# phatdapter.net
KiCad netlist of a schematic drawn in EAGLE
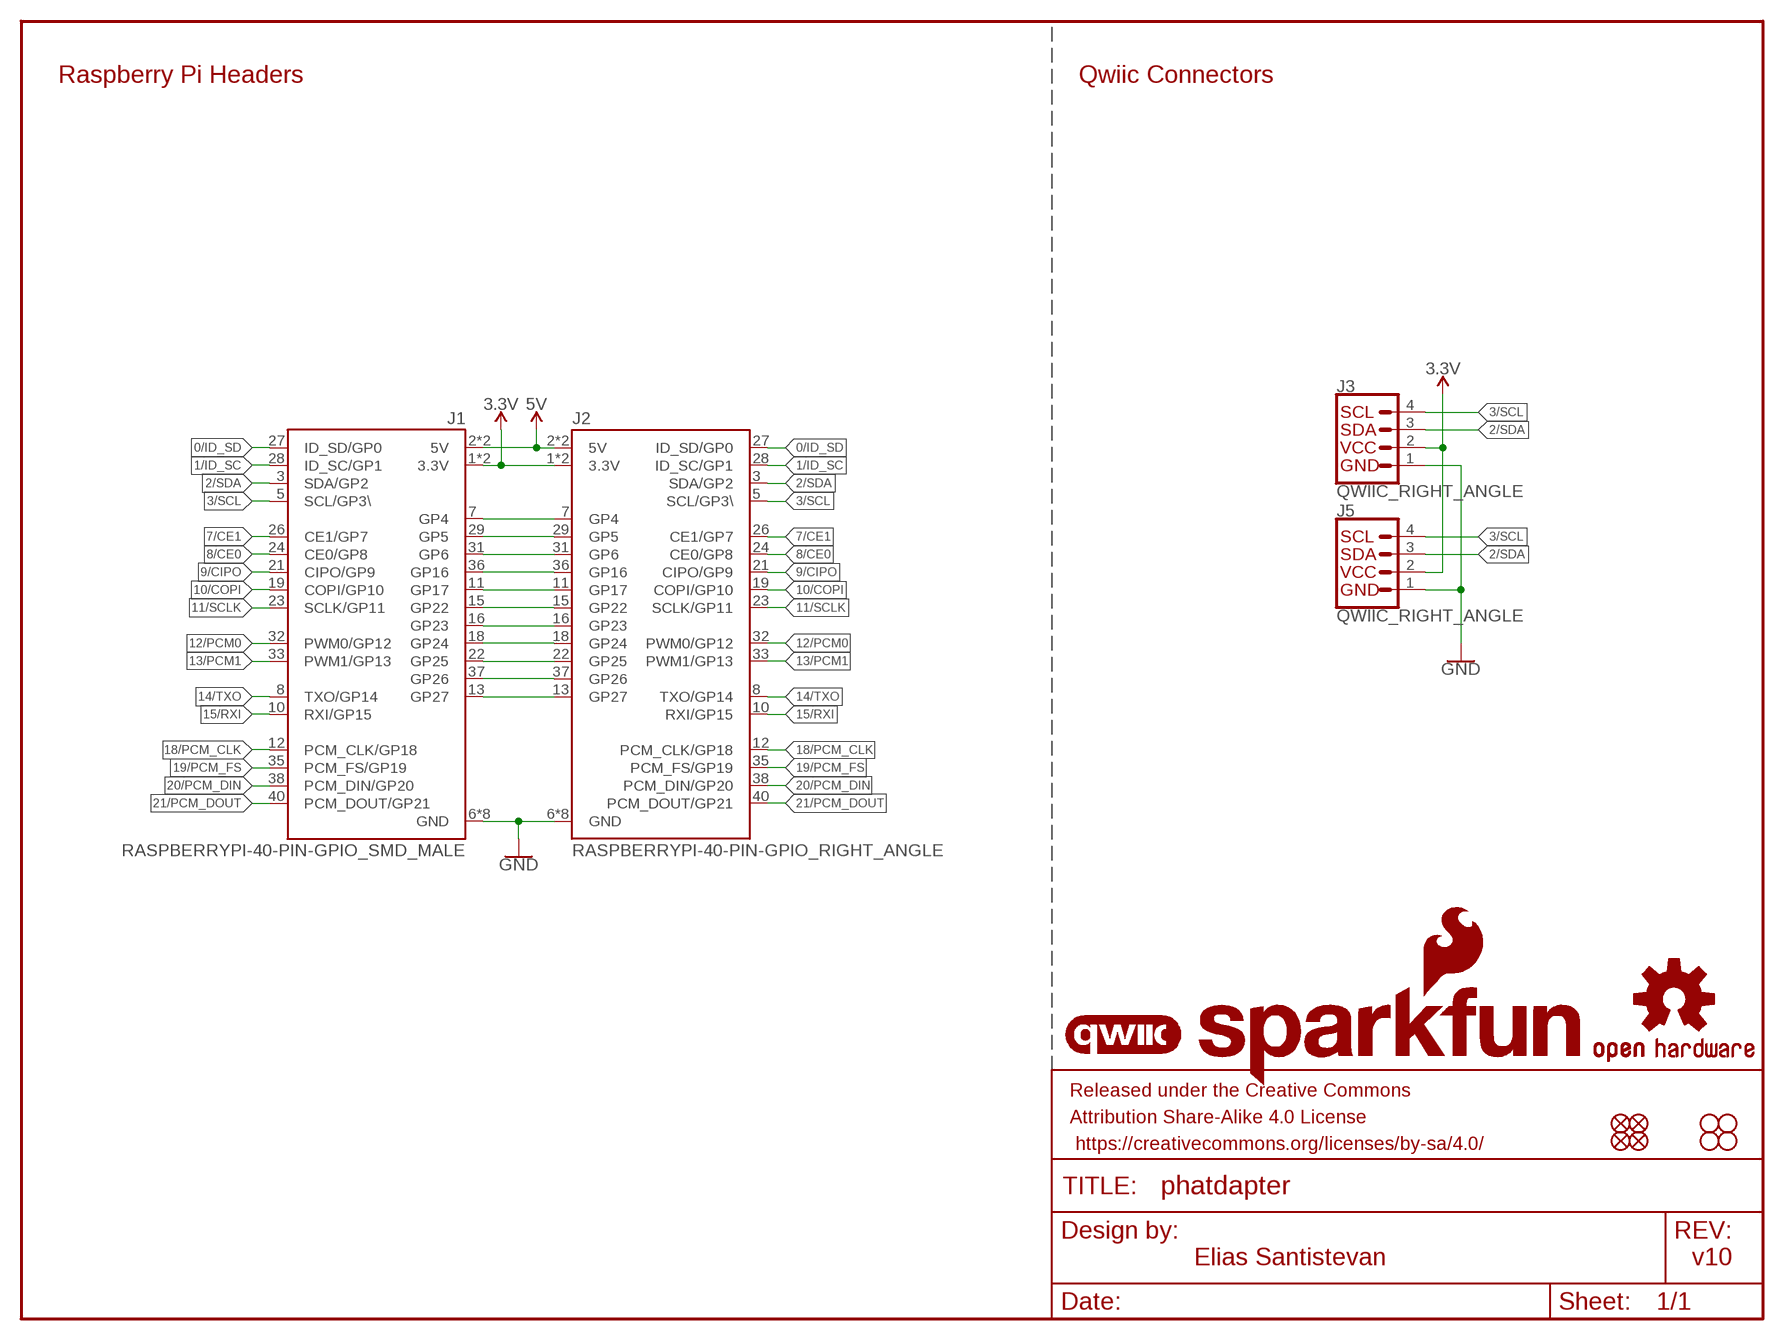
[diagram p0: schematic, sheet 1]

(export (version "E")
  (design (tool "Eeschema 10.0.6"))
  (components
    (comp (ref "FD1")
      (value "FIDUCIALUFIDUCIAL")
      (footprint "eagle-import:FIDUCIAL-MICRO")
      (libsource (lib "eagle-import") (part "FIDUCIALUFIDUCIAL"))
    )
    (comp (ref "FD2")
      (value "FIDUCIALUFIDUCIAL")
      (footprint "eagle-import:FIDUCIAL-MICRO")
      (libsource (lib "eagle-import") (part "FIDUCIALUFIDUCIAL"))
    )
    (comp (ref "FD3")
      (value "FIDUCIALUFIDUCIAL")
      (footprint "eagle-import:FIDUCIAL-MICRO")
      (libsource (lib "eagle-import") (part "FIDUCIALUFIDUCIAL"))
    )
    (comp (ref "FD4")
      (value "FIDUCIALUFIDUCIAL")
      (footprint "eagle-import:FIDUCIAL-MICRO")
      (libsource (lib "eagle-import") (part "FIDUCIALUFIDUCIAL"))
    )
    (comp (ref "FRAME1")
      (value "FRAME-LETTER")
      (footprint "eagle-import:CREATIVE_COMMONS")
      (libsource (lib "eagle-import") (part "FRAME-LETTER"))
    )
    (comp (ref "H1")
      (value "STAND-OFFTIGHT")
      (footprint "eagle-import:STAND-OFF-TIGHT")
      (libsource (lib "eagle-import") (part "STAND-OFFTIGHT"))
    )
    (comp (ref "H2")
      (value "STAND-OFFTIGHT")
      (footprint "eagle-import:STAND-OFF-TIGHT")
      (libsource (lib "eagle-import") (part "STAND-OFFTIGHT"))
    )
    (comp (ref "H3")
      (value "STAND-OFFTIGHT")
      (footprint "eagle-import:STAND-OFF-TIGHT")
      (libsource (lib "eagle-import") (part "STAND-OFFTIGHT"))
    )
    (comp (ref "H4")
      (value "STAND-OFFTIGHT")
      (footprint "eagle-import:STAND-OFF-TIGHT")
      (libsource (lib "eagle-import") (part "STAND-OFFTIGHT"))
    )
    (comp (ref "J1")
      (value "RASPBERRYPI-40-PIN-GPIO_SMD_MALE")
      (footprint "eagle-import:RASPBERRY_PI_HAT_40_PIN_SMD_MALE")
      (libsource (lib "eagle-import") (part "RASPBERRYPI-40-PIN-GPIO_SMD_MALE"))
    )
    (comp (ref "J2")
      (value "RASPBERRYPI-40-PIN-GPIO_RIGHT_ANGLE")
      (footprint "eagle-import:2X20_RIGHT_ANGLE")
      (libsource (lib "eagle-import") (part "RASPBERRYPI-40-PIN-GPIO_RIGHT_ANGLE"))
    )
    (comp (ref "J3")
      (value "QWIIC_RIGHT_ANGLE")
      (footprint "eagle-import:JST04_1MM_RA")
      (libsource (lib "eagle-import") (part "QWIIC_CONNECTORJS-1MM"))
    )
    (comp (ref "J5")
      (value "QWIIC_RIGHT_ANGLE")
      (footprint "eagle-import:JST04_1MM_RA")
      (libsource (lib "eagle-import") (part "QWIIC_CONNECTORJS-1MM"))
    )
    (comp (ref "LOGO1")
      (value "QWIIC_LOGO_5MM")
      (footprint "eagle-import:QWIIC_5MM")
      (libsource (lib "eagle-import") (part "QWIIC_LOGO_5MM"))
    )
    (comp (ref "LOGO2")
      (value "SFE_LOGO_NAME_FLAME.4_INCH")
      (footprint "eagle-import:SFE_LOGO_NAME_FLAME_.4")
      (libsource (lib "eagle-import") (part "SFE_LOGO_NAME_FLAME.4_INCH"))
    )
    (comp (ref "LOGO3")
      (value "OSHW-LOGOM")
      (footprint "eagle-import:OSHW-LOGO-M")
      (libsource (lib "eagle-import") (part "OSHW-LOGOM"))
    )
  )
  (nets
    (net (code "1") (name "0{slash}ID_SD") (class "Default")
      (node (ref "J1") (pin "27") (pinfunction "ID_SD/GP0_27") (pintype "bidirectional"))
      (node (ref "J2") (pin "27") (pinfunction "ID_SD/GP0_27") (pintype "bidirectional"))
    )
    (net (code "2") (name "1{slash}ID_SC") (class "Default")
      (node (ref "J1") (pin "28") (pinfunction "ID_SC/GP1_28") (pintype "bidirectional"))
      (node (ref "J2") (pin "28") (pinfunction "ID_SC/GP1_28") (pintype "bidirectional"))
    )
    (net (code "3") (name "2{slash}SDA") (class "Default")
      (node (ref "J1") (pin "3") (pinfunction "SDA/GP2_3") (pintype "bidirectional"))
      (node (ref "J2") (pin "3") (pinfunction "SDA/GP2_3") (pintype "bidirectional"))
      (node (ref "J3") (pin "3") (pinfunction "3_3") (pintype "passive"))
      (node (ref "J5") (pin "3") (pinfunction "3_3") (pintype "passive"))
    )
    (net (code "4") (name "3.3V") (class "Default")
      (node (ref "J1") (pin "1") (pinfunction "3.3V_1") (pintype "power_in"))
      (node (ref "J1") (pin "17") (pinfunction "3.3V_17") (pintype "power_in"))
      (node (ref "J2") (pin "1") (pinfunction "3.3V_1") (pintype "power_in"))
      (node (ref "J2") (pin "17") (pinfunction "3.3V_17") (pintype "power_in"))
      (node (ref "J3") (pin "2") (pinfunction "2_2") (pintype "power_in"))
      (node (ref "J5") (pin "2") (pinfunction "2_2") (pintype "power_in"))
    )
    (net (code "5") (name "3{slash}SCL") (class "Default")
      (node (ref "J1") (pin "5") (pinfunction "SCL/GP3\\_5") (pintype "bidirectional"))
      (node (ref "J2") (pin "5") (pinfunction "SCL/GP3\\_5") (pintype "bidirectional"))
      (node (ref "J3") (pin "4") (pinfunction "4_4") (pintype "passive"))
      (node (ref "J5") (pin "4") (pinfunction "4_4") (pintype "passive"))
    )
    (net (code "6") (name "5V") (class "Default")
      (node (ref "J1") (pin "2") (pinfunction "5V_2") (pintype "power_in"))
      (node (ref "J1") (pin "4") (pinfunction "5V_4") (pintype "power_in"))
      (node (ref "J2") (pin "2") (pinfunction "5V_2") (pintype "power_in"))
      (node (ref "J2") (pin "4") (pinfunction "5V_4") (pintype "power_in"))
    )
    (net (code "7") (name "7{slash}CE1") (class "Default")
      (node (ref "J1") (pin "26") (pinfunction "CE1/GP7_26") (pintype "output"))
      (node (ref "J2") (pin "26") (pinfunction "CE1/GP7_26") (pintype "output"))
    )
    (net (code "8") (name "8{slash}CE0") (class "Default")
      (node (ref "J1") (pin "24") (pinfunction "CE0/GP8_24") (pintype "output"))
      (node (ref "J2") (pin "24") (pinfunction "CE0/GP8_24") (pintype "output"))
    )
    (net (code "9") (name "9{slash}CIPO") (class "Default")
      (node (ref "J1") (pin "21") (pinfunction "CIPO/GP9_21") (pintype "input"))
      (node (ref "J2") (pin "21") (pinfunction "CIPO/GP9_21") (pintype "input"))
    )
    (net (code "10") (name "10{slash}COPI") (class "Default")
      (node (ref "J1") (pin "19") (pinfunction "COPI/GP10_19") (pintype "output"))
      (node (ref "J2") (pin "19") (pinfunction "COPI/GP10_19") (pintype "output"))
    )
    (net (code "11") (name "11{slash}SCLK") (class "Default")
      (node (ref "J1") (pin "23") (pinfunction "SCLK/GP11_23") (pintype "output"))
      (node (ref "J2") (pin "23") (pinfunction "SCLK/GP11_23") (pintype "output"))
    )
    (net (code "12") (name "12{slash}PCM0") (class "Default")
      (node (ref "J1") (pin "32") (pinfunction "PWM0/GP12_32") (pintype "bidirectional"))
      (node (ref "J2") (pin "32") (pinfunction "PWM0/GP12_32") (pintype "bidirectional"))
    )
    (net (code "13") (name "13{slash}PCM1") (class "Default")
      (node (ref "J1") (pin "33") (pinfunction "PWM1/GP13_33") (pintype "bidirectional"))
      (node (ref "J2") (pin "33") (pinfunction "PWM1/GP13_33") (pintype "bidirectional"))
    )
    (net (code "14") (name "14{slash}TXO") (class "Default")
      (node (ref "J1") (pin "8") (pinfunction "TXO/GP14_8") (pintype "output"))
      (node (ref "J2") (pin "8") (pinfunction "TXO/GP14_8") (pintype "output"))
    )
    (net (code "15") (name "15{slash}RXI") (class "Default")
      (node (ref "J1") (pin "10") (pinfunction "RXI/GP15_10") (pintype "input"))
      (node (ref "J2") (pin "10") (pinfunction "RXI/GP15_10") (pintype "input"))
    )
    (net (code "16") (name "18{slash}PCM_CLK") (class "Default")
      (node (ref "J1") (pin "12") (pinfunction "PCM_CLK/GP18_12") (pintype "bidirectional"))
      (node (ref "J2") (pin "12") (pinfunction "PCM_CLK/GP18_12") (pintype "bidirectional"))
    )
    (net (code "17") (name "19{slash}PCM_FS") (class "Default")
      (node (ref "J1") (pin "35") (pinfunction "PCM_FS/GP19_35") (pintype "bidirectional"))
      (node (ref "J2") (pin "35") (pinfunction "PCM_FS/GP19_35") (pintype "bidirectional"))
    )
    (net (code "18") (name "20{slash}PCM_DIN") (class "Default")
      (node (ref "J1") (pin "38") (pinfunction "PCM_DIN/GP20_38") (pintype "bidirectional"))
      (node (ref "J2") (pin "38") (pinfunction "PCM_DIN/GP20_38") (pintype "bidirectional"))
    )
    (net (code "19") (name "21{slash}PCM_DOUT") (class "Default")
      (node (ref "J1") (pin "40") (pinfunction "PCM_DOUT/GP21_40") (pintype "bidirectional"))
      (node (ref "J2") (pin "40") (pinfunction "PCM_DOUT/GP21_40") (pintype "bidirectional"))
    )
    (net (code "20") (name "GND") (class "Default")
      (node (ref "J1") (pin "14") (pinfunction "GND_14") (pintype "power_in"))
      (node (ref "J1") (pin "20") (pinfunction "GND_20") (pintype "power_in"))
      (node (ref "J1") (pin "25") (pinfunction "GND_25") (pintype "power_in"))
      (node (ref "J1") (pin "30") (pinfunction "GND_30") (pintype "power_in"))
      (node (ref "J1") (pin "34") (pinfunction "GND_34") (pintype "power_in"))
      (node (ref "J1") (pin "39") (pinfunction "GND_39") (pintype "power_in"))
      (node (ref "J1") (pin "6") (pinfunction "GND_6") (pintype "power_in"))
      (node (ref "J1") (pin "9") (pinfunction "GND_9") (pintype "power_in"))
      (node (ref "J2") (pin "14") (pinfunction "GND_14") (pintype "power_in"))
      (node (ref "J2") (pin "20") (pinfunction "GND_20") (pintype "power_in"))
      (node (ref "J2") (pin "25") (pinfunction "GND_25") (pintype "power_in"))
      (node (ref "J2") (pin "30") (pinfunction "GND_30") (pintype "power_in"))
      (node (ref "J2") (pin "34") (pinfunction "GND_34") (pintype "power_in"))
      (node (ref "J2") (pin "39") (pinfunction "GND_39") (pintype "power_in"))
      (node (ref "J2") (pin "6") (pinfunction "GND_6") (pintype "power_in"))
      (node (ref "J2") (pin "9") (pinfunction "GND_9") (pintype "power_in"))
      (node (ref "J3") (pin "1") (pinfunction "1_1") (pintype "power_in"))
      (node (ref "J5") (pin "1") (pinfunction "1_1") (pintype "power_in"))
    )
    (net (code "21") (name "Net-(J1-GP4)") (class "Default")
      (node (ref "J1") (pin "7") (pinfunction "GP4_7") (pintype "bidirectional"))
      (node (ref "J2") (pin "7") (pinfunction "GP4_7") (pintype "bidirectional"))
    )
    (net (code "22") (name "Net-(J1-GP5)") (class "Default")
      (node (ref "J1") (pin "29") (pinfunction "GP5_29") (pintype "bidirectional"))
      (node (ref "J2") (pin "29") (pinfunction "GP5_29") (pintype "bidirectional"))
    )
    (net (code "23") (name "Net-(J1-GP6)") (class "Default")
      (node (ref "J1") (pin "31") (pinfunction "GP6_31") (pintype "bidirectional"))
      (node (ref "J2") (pin "31") (pinfunction "GP6_31") (pintype "bidirectional"))
    )
    (net (code "24") (name "Net-(J1-GP16)") (class "Default")
      (node (ref "J1") (pin "36") (pinfunction "GP16_36") (pintype "bidirectional"))
      (node (ref "J2") (pin "36") (pinfunction "GP16_36") (pintype "bidirectional"))
    )
    (net (code "25") (name "Net-(J1-GP17)") (class "Default")
      (node (ref "J1") (pin "11") (pinfunction "GP17_11") (pintype "bidirectional"))
      (node (ref "J2") (pin "11") (pinfunction "GP17_11") (pintype "bidirectional"))
    )
    (net (code "26") (name "Net-(J1-GP22)") (class "Default")
      (node (ref "J1") (pin "15") (pinfunction "GP22_15") (pintype "bidirectional"))
      (node (ref "J2") (pin "15") (pinfunction "GP22_15") (pintype "bidirectional"))
    )
    (net (code "27") (name "Net-(J1-GP23)") (class "Default")
      (node (ref "J1") (pin "16") (pinfunction "GP23_16") (pintype "bidirectional"))
      (node (ref "J2") (pin "16") (pinfunction "GP23_16") (pintype "bidirectional"))
    )
    (net (code "28") (name "Net-(J1-GP24)") (class "Default")
      (node (ref "J1") (pin "18") (pinfunction "GP24_18") (pintype "bidirectional"))
      (node (ref "J2") (pin "18") (pinfunction "GP24_18") (pintype "bidirectional"))
    )
    (net (code "29") (name "Net-(J1-GP25)") (class "Default")
      (node (ref "J1") (pin "22") (pinfunction "GP25_22") (pintype "bidirectional"))
      (node (ref "J2") (pin "22") (pinfunction "GP25_22") (pintype "bidirectional"))
    )
    (net (code "30") (name "Net-(J1-GP26)") (class "Default")
      (node (ref "J1") (pin "37") (pinfunction "GP26_37") (pintype "bidirectional"))
      (node (ref "J2") (pin "37") (pinfunction "GP26_37") (pintype "bidirectional"))
    )
    (net (code "31") (name "Net-(J1-GP27)") (class "Default")
      (node (ref "J1") (pin "13") (pinfunction "GP27_13") (pintype "bidirectional"))
      (node (ref "J2") (pin "13") (pinfunction "GP27_13") (pintype "bidirectional"))
    )
  )
)
